# GC2-xHAT-v1_0.net
KiCad netlist of a schematic drawn in EAGLE
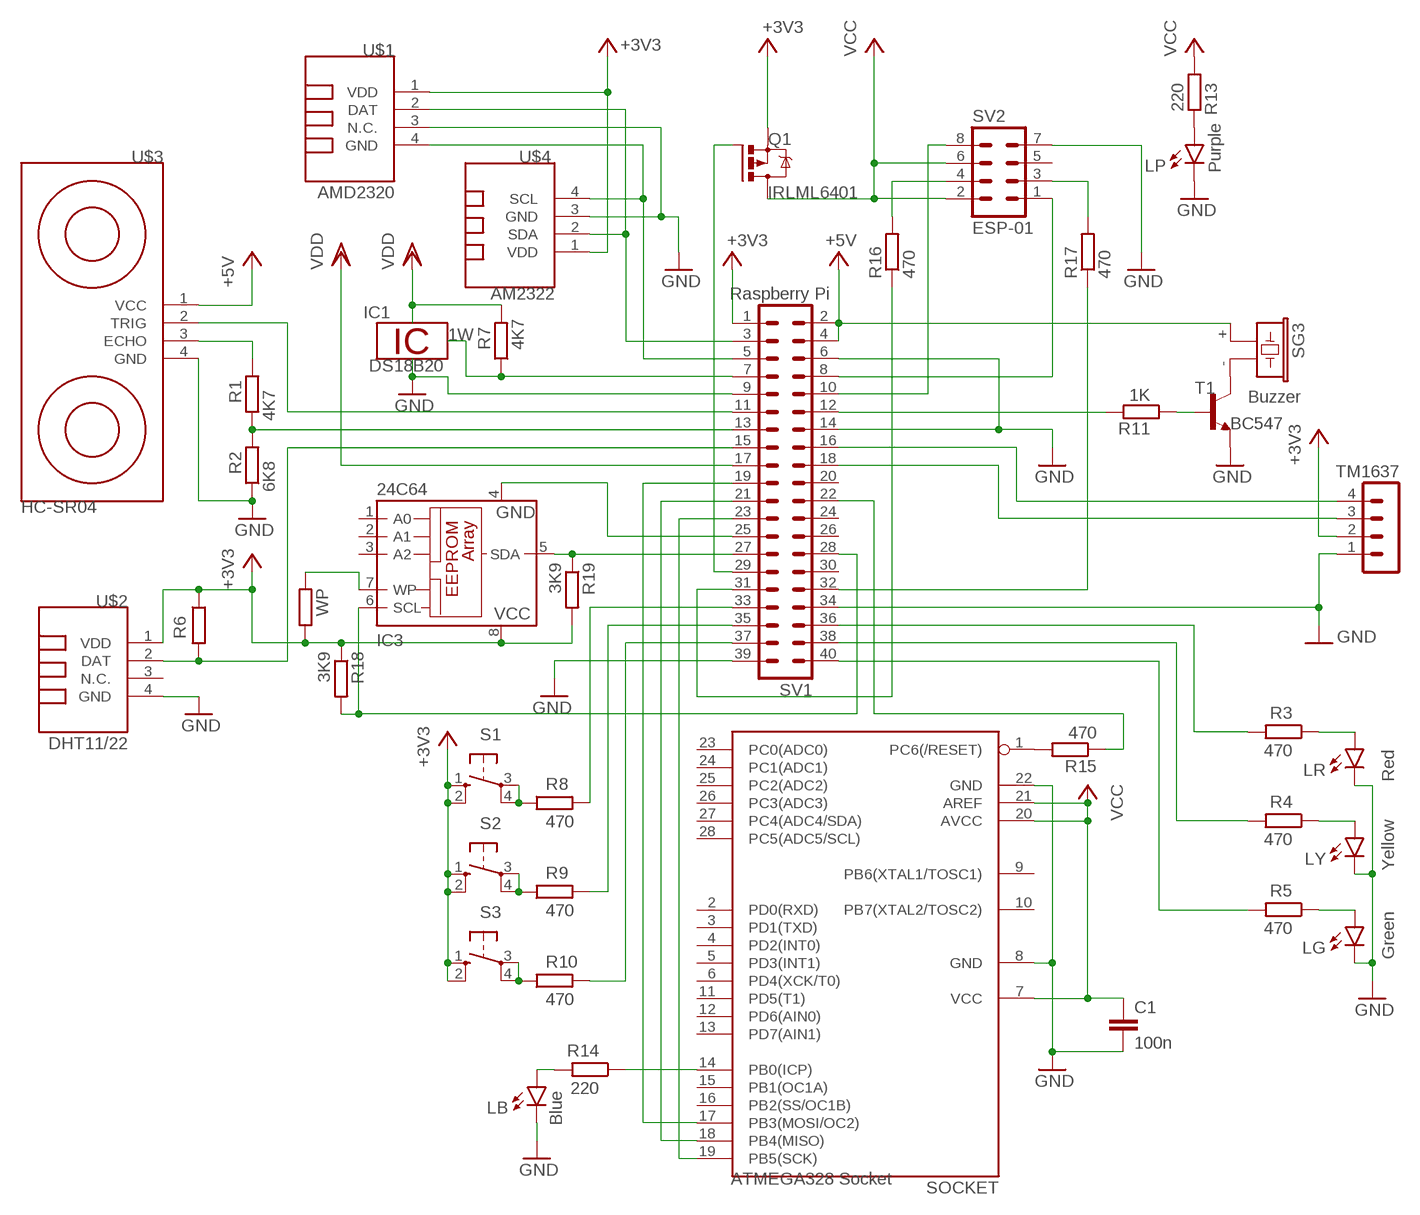
[diagram p0: schematic, sheet 1]

(export (version "E")
  (design (tool "Eeschema 10.0.6"))
  (components
    (comp (ref "C1")
      (value "100n")
      (footprint "eagle-import:C025-024X044")
      (libsource (lib "eagle-import") (part "C-EU025-024X044"))
    )
    (comp (ref "IC1")
      (value "DS18B20")
      (footprint "eagle-import:TO92-")
      (libsource (lib "eagle-import") (part "DS18B20"))
    )
    (comp (ref "IC3")
      (value "24C64")
      (footprint "eagle-import:SO-08")
      (fields (field (name "MPN") "IS24C32A-2GLI"))
      (libsource (lib "eagle-import") (part "24SNC32A"))
    )
    (comp (ref "LB")
      (value "Blue")
      (footprint "eagle-import:LED3MM")
      (libsource (lib "eagle-import") (part "LED3MM"))
    )
    (comp (ref "LG")
      (value "Green")
      (footprint "eagle-import:LED3MM")
      (libsource (lib "eagle-import") (part "LED3MM"))
    )
    (comp (ref "LP")
      (value "Purple")
      (footprint "eagle-import:LED3MM")
      (libsource (lib "eagle-import") (part "LED3MM"))
    )
    (comp (ref "LR")
      (value "Red")
      (footprint "eagle-import:LED3MM")
      (libsource (lib "eagle-import") (part "LED3MM"))
    )
    (comp (ref "LY")
      (value "Yellow")
      (footprint "eagle-import:LED3MM")
      (libsource (lib "eagle-import") (part "LED3MM"))
    )
    (comp (ref "Q1")
      (value "IRLML6401")
      (footprint "eagle-import:MICRO3")
      (libsource (lib "eagle-import") (part "IRLML5203"))
    )
    (comp (ref "R1")
      (value "4K7")
      (footprint "eagle-import:0309V")
      (libsource (lib "eagle-import") (part "R-EU_0309/V"))
    )
    (comp (ref "R2")
      (value "6K8")
      (footprint "eagle-import:0309V")
      (libsource (lib "eagle-import") (part "R-EU_0309/V"))
    )
    (comp (ref "R3")
      (value "470")
      (footprint "eagle-import:0309V")
      (libsource (lib "eagle-import") (part "R-EU_0309/V"))
    )
    (comp (ref "R4")
      (value "470")
      (footprint "eagle-import:0309V")
      (libsource (lib "eagle-import") (part "R-EU_0309/V"))
    )
    (comp (ref "R5")
      (value "470")
      (footprint "eagle-import:0309V")
      (libsource (lib "eagle-import") (part "R-EU_0309/V"))
    )
    (comp (ref "R6")
      (value "4K7")
      (footprint "eagle-import:0309V")
      (libsource (lib "eagle-import") (part "R-EU_0309/V"))
    )
    (comp (ref "R7")
      (value "4K7")
      (footprint "eagle-import:0309V")
      (libsource (lib "eagle-import") (part "R-EU_0309/V"))
    )
    (comp (ref "R8")
      (value "470")
      (footprint "eagle-import:0309V")
      (libsource (lib "eagle-import") (part "R-EU_0309/V"))
    )
    (comp (ref "R9")
      (value "470")
      (footprint "eagle-import:0309V")
      (libsource (lib "eagle-import") (part "R-EU_0309/V"))
    )
    (comp (ref "R10")
      (value "470")
      (footprint "eagle-import:0309V")
      (libsource (lib "eagle-import") (part "R-EU_0309/V"))
    )
    (comp (ref "R11")
      (value "1K")
      (footprint "eagle-import:0309V")
      (libsource (lib "eagle-import") (part "R-EU_0309/V"))
    )
    (comp (ref "R13")
      (value "220")
      (footprint "eagle-import:0309V")
      (libsource (lib "eagle-import") (part "R-EU_0309/V"))
    )
    (comp (ref "R14")
      (value "220")
      (footprint "eagle-import:0309V")
      (libsource (lib "eagle-import") (part "R-EU_0309/V"))
    )
    (comp (ref "R15")
      (value "470")
      (footprint "eagle-import:0204_7")
      (libsource (lib "eagle-import") (part "R-EU_0204/7"))
    )
    (comp (ref "R16")
      (value "470")
      (footprint "eagle-import:0204_7")
      (libsource (lib "eagle-import") (part "R-EU_0204/7"))
    )
    (comp (ref "R17")
      (value "470")
      (footprint "eagle-import:0204_7")
      (libsource (lib "eagle-import") (part "R-EU_0204/7"))
    )
    (comp (ref "R18")
      (value "3K9")
      (footprint "eagle-import:R1206")
      (libsource (lib "eagle-import") (part "R-EU_R1206"))
    )
    (comp (ref "R19")
      (value "3K9")
      (footprint "eagle-import:R1206")
      (libsource (lib "eagle-import") (part "R-EU_R1206"))
    )
    (comp (ref "S1")
      (value "10-XX")
      (footprint "eagle-import:B3F-10XX")
      (fields (field (name "MPN") "B3F-1000"))
      (libsource (lib "eagle-import") (part "10-XX"))
    )
    (comp (ref "S2")
      (value "10-XX")
      (footprint "eagle-import:B3F-10XX")
      (fields (field (name "MPN") "B3F-1000"))
      (libsource (lib "eagle-import") (part "10-XX"))
    )
    (comp (ref "S3")
      (value "10-XX")
      (footprint "eagle-import:B3F-10XX")
      (fields (field (name "MPN") "B3F-1000"))
      (libsource (lib "eagle-import") (part "10-XX"))
    )
    (comp (ref "SG3")
      (value "Buzzer")
      (footprint "eagle-import:F_CM12P")
      (libsource (lib "eagle-import") (part "F/CM12P"))
    )
    (comp (ref "SOCKET")
      (value "ATMEGA328 Socket")
      (footprint "eagle-import:DIL28-3")
      (libsource (lib "eagle-import") (part "MEGA8-P"))
    )
    (comp (ref "SV1")
      (value "Raspberry Pi")
      (footprint "eagle-import:MA20-2")
      (libsource (lib "eagle-import") (part "MA20-2"))
    )
    (comp (ref "SV2")
      (value "ESP-01")
      (footprint "eagle-import:MA04-2")
      (libsource (lib "eagle-import") (part "MA04-2"))
    )
    (comp (ref "SW")
      (value "WP")
      (footprint "eagle-import:M1406")
      (libsource (lib "eagle-import") (part "R-EU_M1406"))
    )
    (comp (ref "T1")
      (value "BC547")
      (footprint "eagle-import:TO92")
      (libsource (lib "eagle-import") (part "BC547"))
    )
    (comp (ref "TM1637")
      (value "MA04-1")
      (footprint "eagle-import:MA04-1")
      (libsource (lib "eagle-import") (part "MA04-1"))
    )
    (comp (ref "U$1")
      (value "AMD2320")
      (footprint "eagle-import:TEMP-HUM-SENSOR-DHT11")
      (libsource (lib "eagle-import") (part "TEMP-HUM-SENSOR-DHT11"))
    )
    (comp (ref "U$2")
      (value "DHT11/22")
      (footprint "eagle-import:TEMP-HUM-SENSOR-DHT11")
      (libsource (lib "eagle-import") (part "TEMP-HUM-SENSOR-DHT11"))
    )
    (comp (ref "U$3")
      (value "HC-SR04")
      (footprint "eagle-import:ULTRASONIC-HC-SR04#V")
      (libsource (lib "eagle-import") (part "ULTRASONIC-HC-SR04#V"))
    )
    (comp (ref "U$4")
      (value "AM2322")
      (footprint "eagle-import:TEMP-HUM-SENSOR-AM2322")
      (libsource (lib "eagle-import") (part "TEMP-HUM-SENSOR-AM2322"))
    )
  )
  (nets
    (net (code "1") (name "+3V3") (class "Default")
      (node (ref "IC3") (pin "8") (pinfunction "VCC_8") (pintype "power_in"))
      (node (ref "Q1") (pin "2") (pinfunction "S_2") (pintype "passive"))
      (node (ref "R18") (pin "1") (pinfunction "1_1") (pintype "passive"))
      (node (ref "R19") (pin "2") (pinfunction "2_2") (pintype "passive"))
      (node (ref "R6") (pin "1") (pinfunction "1_1") (pintype "passive"))
      (node (ref "S1") (pin "1") (pinfunction "S_1") (pintype "passive"))
      (node (ref "S1") (pin "2") (pinfunction "S1_2") (pintype "passive"))
      (node (ref "S2") (pin "1") (pinfunction "S_1") (pintype "passive"))
      (node (ref "S2") (pin "2") (pinfunction "S1_2") (pintype "passive"))
      (node (ref "S3") (pin "1") (pinfunction "S_1") (pintype "passive"))
      (node (ref "S3") (pin "2") (pinfunction "S1_2") (pintype "passive"))
      (node (ref "SV1") (pin "1") (pinfunction "1_1") (pintype "passive"))
      (node (ref "SW") (pin "1") (pinfunction "1_1") (pintype "passive"))
      (node (ref "TM1637") (pin "2") (pinfunction "2_2") (pintype "passive"))
      (node (ref "U$1") (pin "1") (pinfunction "VDD_1") (pintype "power_in"))
      (node (ref "U$2") (pin "1") (pinfunction "VDD_1") (pintype "power_in"))
      (node (ref "U$4") (pin "1") (pinfunction "VDD_1") (pintype "power_in"))
    )
    (net (code "2") (name "+5V") (class "Default")
      (node (ref "SG3") (pin "+") (pinfunction "1_+") (pintype "passive"))
      (node (ref "SV1") (pin "2") (pinfunction "2_2") (pintype "passive"))
      (node (ref "SV1") (pin "4") (pinfunction "4_4") (pintype "passive"))
      (node (ref "U$3") (pin "1") (pinfunction "VCC_1") (pintype "power_in"))
    )
    (net (code "3") (name "/1W") (class "Default")
      (node (ref "R7") (pin "1") (pinfunction "1_1") (pintype "passive"))
      (node (ref "SV1") (pin "7") (pinfunction "7_7") (pintype "passive"))
    )
    (net (code "4") (name "GND") (class "Default")
      (node (ref "C1") (pin "2") (pinfunction "2_2") (pintype "passive"))
      (node (ref "LB") (pin "K") (pinfunction "C_K") (pintype "passive"))
      (node (ref "LG") (pin "K") (pinfunction "C_K") (pintype "passive"))
      (node (ref "LP") (pin "K") (pinfunction "C_K") (pintype "passive"))
      (node (ref "LR") (pin "K") (pinfunction "C_K") (pintype "passive"))
      (node (ref "LY") (pin "K") (pinfunction "C_K") (pintype "passive"))
      (node (ref "R2") (pin "1") (pinfunction "1_1") (pintype "passive"))
      (node (ref "SOCKET") (pin "22") (pinfunction "GND_22") (pintype "power_in"))
      (node (ref "SOCKET") (pin "8") (pinfunction "GND_8") (pintype "power_in"))
      (node (ref "SV1") (pin "14") (pinfunction "14_14") (pintype "passive"))
      (node (ref "SV1") (pin "34") (pinfunction "34_34") (pintype "passive"))
      (node (ref "SV1") (pin "39") (pinfunction "39_39") (pintype "passive"))
      (node (ref "SV1") (pin "6") (pinfunction "6_6") (pintype "passive"))
      (node (ref "SV1") (pin "9") (pinfunction "9_9") (pintype "passive"))
      (node (ref "SV2") (pin "7") (pinfunction "7_7") (pintype "passive"))
      (node (ref "T1") (pin "1") (pinfunction "E_1") (pintype "passive"))
      (node (ref "TM1637") (pin "1") (pinfunction "1_1") (pintype "passive"))
      (node (ref "U$1") (pin "3") (pinfunction "N.C._3") (pintype "passive"))
      (node (ref "U$2") (pin "4") (pinfunction "GND_4") (pintype "power_in"))
      (node (ref "U$3") (pin "4") (pinfunction "GND_4") (pintype "power_in"))
      (node (ref "U$4") (pin "3") (pinfunction "GND_3") (pintype "power_in"))
    )
    (net (code "5") (name "Net-(IC3-GND)") (class "Default")
      (node (ref "IC3") (pin "4") (pinfunction "GND_4") (pintype "power_in"))
      (node (ref "SV1") (pin "25") (pinfunction "25_25") (pintype "passive"))
    )
    (net (code "6") (name "Net-(IC3-SCL)") (class "Default")
      (node (ref "IC3") (pin "6") (pinfunction "SCL_6") (pintype "input"))
      (node (ref "R18") (pin "2") (pinfunction "2_2") (pintype "passive"))
      (node (ref "SV1") (pin "28") (pinfunction "28_28") (pintype "passive"))
    )
    (net (code "7") (name "Net-(IC3-SDA)") (class "Default")
      (node (ref "IC3") (pin "5") (pinfunction "SDA_5") (pintype "bidirectional"))
      (node (ref "R19") (pin "1") (pinfunction "1_1") (pintype "passive"))
      (node (ref "SV1") (pin "27") (pinfunction "27_27") (pintype "passive"))
    )
    (net (code "8") (name "Net-(IC3-WP)") (class "Default")
      (node (ref "IC3") (pin "7") (pinfunction "WP_7") (pintype "input"))
      (node (ref "SW") (pin "2") (pinfunction "2_2") (pintype "passive"))
    )
    (net (code "9") (name "Net-(LB-PadA)") (class "Default")
      (node (ref "LB") (pin "A") (pinfunction "A_A") (pintype "passive"))
      (node (ref "R14") (pin "2") (pinfunction "2_2") (pintype "passive"))
    )
    (net (code "10") (name "Net-(LG-PadA)") (class "Default")
      (node (ref "LG") (pin "A") (pinfunction "A_A") (pintype "passive"))
      (node (ref "R5") (pin "1") (pinfunction "1_1") (pintype "passive"))
    )
    (net (code "11") (name "Net-(LP-PadA)") (class "Default")
      (node (ref "LP") (pin "A") (pinfunction "A_A") (pintype "passive"))
      (node (ref "R13") (pin "2") (pinfunction "2_2") (pintype "passive"))
    )
    (net (code "12") (name "Net-(LR-PadA)") (class "Default")
      (node (ref "LR") (pin "A") (pinfunction "A_A") (pintype "passive"))
      (node (ref "R3") (pin "1") (pinfunction "1_1") (pintype "passive"))
    )
    (net (code "13") (name "Net-(LY-PadA)") (class "Default")
      (node (ref "LY") (pin "A") (pinfunction "A_A") (pintype "passive"))
      (node (ref "R4") (pin "1") (pinfunction "1_1") (pintype "passive"))
    )
    (net (code "14") (name "Net-(Q1-G)") (class "Default")
      (node (ref "Q1") (pin "1") (pinfunction "G_1") (pintype "passive"))
      (node (ref "SV1") (pin "29") (pinfunction "29_29") (pintype "passive"))
    )
    (net (code "15") (name "Net-(R1-Pad1)") (class "Default")
      (node (ref "R1") (pin "1") (pinfunction "1_1") (pintype "passive"))
      (node (ref "R2") (pin "2") (pinfunction "2_2") (pintype "passive"))
      (node (ref "SV1") (pin "13") (pinfunction "13_13") (pintype "passive"))
    )
    (net (code "16") (name "Net-(R3-Pad2)") (class "Default")
      (node (ref "R3") (pin "2") (pinfunction "2_2") (pintype "passive"))
      (node (ref "SV1") (pin "36") (pinfunction "36_36") (pintype "passive"))
    )
    (net (code "17") (name "Net-(R4-Pad2)") (class "Default")
      (node (ref "R4") (pin "2") (pinfunction "2_2") (pintype "passive"))
      (node (ref "SV1") (pin "38") (pinfunction "38_38") (pintype "passive"))
    )
    (net (code "18") (name "Net-(R5-Pad2)") (class "Default")
      (node (ref "R5") (pin "2") (pinfunction "2_2") (pintype "passive"))
      (node (ref "SV1") (pin "40") (pinfunction "40_40") (pintype "passive"))
    )
    (net (code "19") (name "Net-(R8-Pad2)") (class "Default")
      (node (ref "R8") (pin "2") (pinfunction "2_2") (pintype "passive"))
      (node (ref "SV1") (pin "33") (pinfunction "33_33") (pintype "passive"))
    )
    (net (code "20") (name "Net-(R9-Pad2)") (class "Default")
      (node (ref "R9") (pin "2") (pinfunction "2_2") (pintype "passive"))
      (node (ref "SV1") (pin "35") (pinfunction "35_35") (pintype "passive"))
    )
    (net (code "21") (name "Net-(R10-Pad2)") (class "Default")
      (node (ref "R10") (pin "2") (pinfunction "2_2") (pintype "passive"))
      (node (ref "SV1") (pin "37") (pinfunction "37_37") (pintype "passive"))
    )
    (net (code "22") (name "Net-(R11-Pad2)") (class "Default")
      (node (ref "R11") (pin "2") (pinfunction "2_2") (pintype "passive"))
      (node (ref "SV1") (pin "12") (pinfunction "12_12") (pintype "passive"))
    )
    (net (code "23") (name "Net-(R15-Pad1)") (class "Default")
      (node (ref "R15") (pin "1") (pinfunction "1_1") (pintype "passive"))
      (node (ref "SV1") (pin "22") (pinfunction "22_22") (pintype "passive"))
    )
    (net (code "24") (name "Net-(R16-Pad1)") (class "Default")
      (node (ref "R16") (pin "1") (pinfunction "1_1") (pintype "passive"))
      (node (ref "SV1") (pin "31") (pinfunction "31_31") (pintype "passive"))
    )
    (net (code "25") (name "Net-(R16-Pad2)") (class "Default")
      (node (ref "R16") (pin "2") (pinfunction "2_2") (pintype "passive"))
      (node (ref "SV2") (pin "4") (pinfunction "4_4") (pintype "passive"))
    )
    (net (code "26") (name "Net-(R17-Pad1)") (class "Default")
      (node (ref "R17") (pin "1") (pinfunction "1_1") (pintype "passive"))
      (node (ref "SV1") (pin "32") (pinfunction "32_32") (pintype "passive"))
    )
    (net (code "27") (name "Net-(R17-Pad2)") (class "Default")
      (node (ref "R17") (pin "2") (pinfunction "2_2") (pintype "passive"))
      (node (ref "SV2") (pin "3") (pinfunction "3_3") (pintype "passive"))
    )
    (net (code "28") (name "Net-(S1-P)") (class "Default")
      (node (ref "R8") (pin "1") (pinfunction "1_1") (pintype "passive"))
      (node (ref "S1") (pin "3") (pinfunction "P_3") (pintype "passive"))
      (node (ref "S1") (pin "4") (pinfunction "P1_4") (pintype "passive"))
    )
    (net (code "29") (name "Net-(S2-P)") (class "Default")
      (node (ref "R9") (pin "1") (pinfunction "1_1") (pintype "passive"))
      (node (ref "S2") (pin "3") (pinfunction "P_3") (pintype "passive"))
      (node (ref "S2") (pin "4") (pinfunction "P1_4") (pintype "passive"))
    )
    (net (code "30") (name "Net-(S3-P)") (class "Default")
      (node (ref "R10") (pin "1") (pinfunction "1_1") (pintype "passive"))
      (node (ref "S3") (pin "3") (pinfunction "P_3") (pintype "passive"))
      (node (ref "S3") (pin "4") (pinfunction "P1_4") (pintype "passive"))
    )
    (net (code "31") (name "Net-(SG3-2)") (class "Default")
      (node (ref "SG3") (pin "-") (pinfunction "2_-") (pintype "passive"))
      (node (ref "T1") (pin "3") (pinfunction "C_3") (pintype "passive"))
    )
    (net (code "32") (name "Net-(SOCKET-PB0(ICP))") (class "Default")
      (node (ref "R14") (pin "1") (pinfunction "1_1") (pintype "passive"))
      (node (ref "SOCKET") (pin "14") (pinfunction "PB0(ICP)_14") (pintype "bidirectional"))
    )
    (net (code "33") (name "Net-(SOCKET-PB3(MOSI{slash}OC2))") (class "Default")
      (node (ref "SOCKET") (pin "17") (pinfunction "PB3(MOSI/OC2)_17") (pintype "bidirectional"))
      (node (ref "SV1") (pin "19") (pinfunction "19_19") (pintype "passive"))
    )
    (net (code "34") (name "Net-(SOCKET-PB4(MISO))") (class "Default")
      (node (ref "SOCKET") (pin "18") (pinfunction "PB4(MISO)_18") (pintype "bidirectional"))
      (node (ref "SV1") (pin "21") (pinfunction "21_21") (pintype "passive"))
    )
    (net (code "35") (name "Net-(SOCKET-PB5(SCK))") (class "Default")
      (node (ref "SOCKET") (pin "19") (pinfunction "PB5(SCK)_19") (pintype "bidirectional"))
      (node (ref "SV1") (pin "23") (pinfunction "23_23") (pintype "passive"))
    )
    (net (code "36") (name "Net-(SOCKET-PC6({slash}RESET))") (class "Default")
      (node (ref "R15") (pin "2") (pinfunction "2_2") (pintype "passive"))
      (node (ref "SOCKET") (pin "1") (pinfunction "PC6(/RESET)_1") (pintype "bidirectional"))
    )
    (net (code "37") (name "Net-(SV1-Pad8)") (class "Default")
      (node (ref "SV1") (pin "8") (pinfunction "8_8") (pintype "passive"))
      (node (ref "SV2") (pin "1") (pinfunction "1_1") (pintype "passive"))
    )
    (net (code "38") (name "Net-(SV1-Pad10)") (class "Default")
      (node (ref "SV1") (pin "10") (pinfunction "10_10") (pintype "passive"))
      (node (ref "SV2") (pin "8") (pinfunction "8_8") (pintype "passive"))
    )
    (net (code "39") (name "Net-(SV1-Pad16)") (class "Default")
      (node (ref "SV1") (pin "16") (pinfunction "16_16") (pintype "passive"))
      (node (ref "TM1637") (pin "4") (pinfunction "4_4") (pintype "passive"))
    )
    (net (code "40") (name "Net-(SV1-Pad18)") (class "Default")
      (node (ref "SV1") (pin "18") (pinfunction "18_18") (pintype "passive"))
      (node (ref "TM1637") (pin "3") (pinfunction "3_3") (pintype "passive"))
    )
    (net (code "41") (name "Net-(T1-B)") (class "Default")
      (node (ref "R11") (pin "1") (pinfunction "1_1") (pintype "passive"))
      (node (ref "T1") (pin "2") (pinfunction "B_2") (pintype "passive"))
    )
    (net (code "42") (name "Net-(U$1-DAT)") (class "Default")
      (node (ref "SV1") (pin "3") (pinfunction "3_3") (pintype "passive"))
      (node (ref "U$1") (pin "2") (pinfunction "DAT_2") (pintype "bidirectional"))
      (node (ref "U$4") (pin "2") (pinfunction "SDA_2") (pintype "bidirectional"))
    )
    (net (code "43") (name "Net-(U$1-GND)") (class "Default")
      (node (ref "SV1") (pin "5") (pinfunction "5_5") (pintype "passive"))
      (node (ref "U$1") (pin "4") (pinfunction "GND_4") (pintype "power_in"))
      (node (ref "U$4") (pin "4") (pinfunction "SCL_4") (pintype "bidirectional"))
    )
    (net (code "44") (name "Net-(U$2-DAT)") (class "Default")
      (node (ref "R6") (pin "2") (pinfunction "2_2") (pintype "passive"))
      (node (ref "SV1") (pin "15") (pinfunction "15_15") (pintype "passive"))
      (node (ref "U$2") (pin "2") (pinfunction "DAT_2") (pintype "bidirectional"))
    )
    (net (code "45") (name "Net-(U$3-ECHO)") (class "Default")
      (node (ref "R1") (pin "2") (pinfunction "2_2") (pintype "passive"))
      (node (ref "U$3") (pin "3") (pinfunction "ECHO_3") (pintype "output"))
    )
    (net (code "46") (name "Net-(U$3-TRIG)") (class "Default")
      (node (ref "SV1") (pin "11") (pinfunction "11_11") (pintype "passive"))
      (node (ref "U$3") (pin "2") (pinfunction "TRIG_2") (pintype "input"))
    )
    (net (code "47") (name "VCC") (class "Default")
      (node (ref "C1") (pin "1") (pinfunction "1_1") (pintype "passive"))
      (node (ref "Q1") (pin "3") (pinfunction "D_3") (pintype "passive"))
      (node (ref "R13") (pin "1") (pinfunction "1_1") (pintype "passive"))
      (node (ref "SOCKET") (pin "20") (pinfunction "AVCC_20") (pintype "power_in"))
      (node (ref "SOCKET") (pin "21") (pinfunction "AREF_21") (pintype "passive"))
      (node (ref "SOCKET") (pin "7") (pinfunction "VCC_7") (pintype "power_in"))
      (node (ref "SV2") (pin "2") (pinfunction "2_2") (pintype "passive"))
      (node (ref "SV2") (pin "6") (pinfunction "6_6") (pintype "passive"))
    )
    (net (code "48") (name "VDD") (class "Default")
      (node (ref "R7") (pin "2") (pinfunction "2_2") (pintype "passive"))
      (node (ref "SV1") (pin "17") (pinfunction "17_17") (pintype "passive"))
    )
    (net (code "49") (name "unconnected-(IC3-A0-Pad1)") (class "Default")
      (node (ref "IC3") (pin "1") (pinfunction "A0_1") (pintype "input"))
    )
    (net (code "50") (name "unconnected-(IC3-A1-Pad2)") (class "Default")
      (node (ref "IC3") (pin "2") (pinfunction "A1_2") (pintype "input"))
    )
    (net (code "51") (name "unconnected-(IC3-A2-Pad3)") (class "Default")
      (node (ref "IC3") (pin "3") (pinfunction "A2_3") (pintype "input"))
    )
    (net (code "52") (name "unconnected-(SOCKET-PB1(OC1A)-Pad15)") (class "Default")
      (node (ref "SOCKET") (pin "15") (pinfunction "PB1(OC1A)_15") (pintype "bidirectional"))
    )
    (net (code "53") (name "unconnected-(SOCKET-PB2(SS{slash}OC1B)-Pad16)") (class "Default")
      (node (ref "SOCKET") (pin "16") (pinfunction "PB2(SS/OC1B)_16") (pintype "bidirectional"))
    )
    (net (code "54") (name "unconnected-(SOCKET-PB6(XTAL1{slash}TOSC1)-Pad9)") (class "Default")
      (node (ref "SOCKET") (pin "9") (pinfunction "PB6(XTAL1/TOSC1)_9") (pintype "bidirectional"))
    )
    (net (code "55") (name "unconnected-(SOCKET-PB7(XTAL2{slash}TOSC2)-Pad10)") (class "Default")
      (node (ref "SOCKET") (pin "10") (pinfunction "PB7(XTAL2/TOSC2)_10") (pintype "bidirectional"))
    )
    (net (code "56") (name "unconnected-(SOCKET-PC0(ADC0)-Pad23)") (class "Default")
      (node (ref "SOCKET") (pin "23") (pinfunction "PC0(ADC0)_23") (pintype "bidirectional"))
    )
    (net (code "57") (name "unconnected-(SOCKET-PC1(ADC1)-Pad24)") (class "Default")
      (node (ref "SOCKET") (pin "24") (pinfunction "PC1(ADC1)_24") (pintype "bidirectional"))
    )
    (net (code "58") (name "unconnected-(SOCKET-PC2(ADC2)-Pad25)") (class "Default")
      (node (ref "SOCKET") (pin "25") (pinfunction "PC2(ADC2)_25") (pintype "bidirectional"))
    )
    (net (code "59") (name "unconnected-(SOCKET-PC3(ADC3)-Pad26)") (class "Default")
      (node (ref "SOCKET") (pin "26") (pinfunction "PC3(ADC3)_26") (pintype "bidirectional"))
    )
    (net (code "60") (name "unconnected-(SOCKET-PC4(ADC4{slash}SDA)-Pad27)") (class "Default")
      (node (ref "SOCKET") (pin "27") (pinfunction "PC4(ADC4/SDA)_27") (pintype "bidirectional"))
    )
    (net (code "61") (name "unconnected-(SOCKET-PC5(ADC5{slash}SCL)-Pad28)") (class "Default")
      (node (ref "SOCKET") (pin "28") (pinfunction "PC5(ADC5/SCL)_28") (pintype "bidirectional"))
    )
    (net (code "62") (name "unconnected-(SOCKET-PD0(RXD)-Pad2)") (class "Default")
      (node (ref "SOCKET") (pin "2") (pinfunction "PD0(RXD)_2") (pintype "bidirectional"))
    )
    (net (code "63") (name "unconnected-(SOCKET-PD1(TXD)-Pad3)") (class "Default")
      (node (ref "SOCKET") (pin "3") (pinfunction "PD1(TXD)_3") (pintype "bidirectional"))
    )
    (net (code "64") (name "unconnected-(SOCKET-PD2(INT0)-Pad4)") (class "Default")
      (node (ref "SOCKET") (pin "4") (pinfunction "PD2(INT0)_4") (pintype "bidirectional"))
    )
    (net (code "65") (name "unconnected-(SOCKET-PD3(INT1)-Pad5)") (class "Default")
      (node (ref "SOCKET") (pin "5") (pinfunction "PD3(INT1)_5") (pintype "bidirectional"))
    )
    (net (code "66") (name "unconnected-(SOCKET-PD4(XCK{slash}T0)-Pad6)") (class "Default")
      (node (ref "SOCKET") (pin "6") (pinfunction "PD4(XCK/T0)_6") (pintype "bidirectional"))
    )
    (net (code "67") (name "unconnected-(SOCKET-PD5(T1)-Pad11)") (class "Default")
      (node (ref "SOCKET") (pin "11") (pinfunction "PD5(T1)_11") (pintype "bidirectional"))
    )
    (net (code "68") (name "unconnected-(SOCKET-PD6(AIN0)-Pad12)") (class "Default")
      (node (ref "SOCKET") (pin "12") (pinfunction "PD6(AIN0)_12") (pintype "bidirectional"))
    )
    (net (code "69") (name "unconnected-(SOCKET-PD7(AIN1)-Pad13)") (class "Default")
      (node (ref "SOCKET") (pin "13") (pinfunction "PD7(AIN1)_13") (pintype "bidirectional"))
    )
    (net (code "70") (name "unconnected-(SV1-Pad20)") (class "Default")
      (node (ref "SV1") (pin "20") (pinfunction "20_20") (pintype "passive"))
    )
    (net (code "71") (name "unconnected-(SV1-Pad24)") (class "Default")
      (node (ref "SV1") (pin "24") (pinfunction "24_24") (pintype "passive"))
    )
    (net (code "72") (name "unconnected-(SV1-Pad26)") (class "Default")
      (node (ref "SV1") (pin "26") (pinfunction "26_26") (pintype "passive"))
    )
    (net (code "73") (name "unconnected-(SV1-Pad30)") (class "Default")
      (node (ref "SV1") (pin "30") (pinfunction "30_30") (pintype "passive"))
    )
    (net (code "74") (name "unconnected-(SV2-Pad5)") (class "Default")
      (node (ref "SV2") (pin "5") (pinfunction "5_5") (pintype "passive"))
    )
    (net (code "75") (name "unconnected-(U$2-N.C.-Pad3)") (class "Default")
      (node (ref "U$2") (pin "3") (pinfunction "N.C._3") (pintype "passive"))
    )
  )
)
